# SensorTemperatura.net
KiCad netlist of a schematic drawn in EAGLE
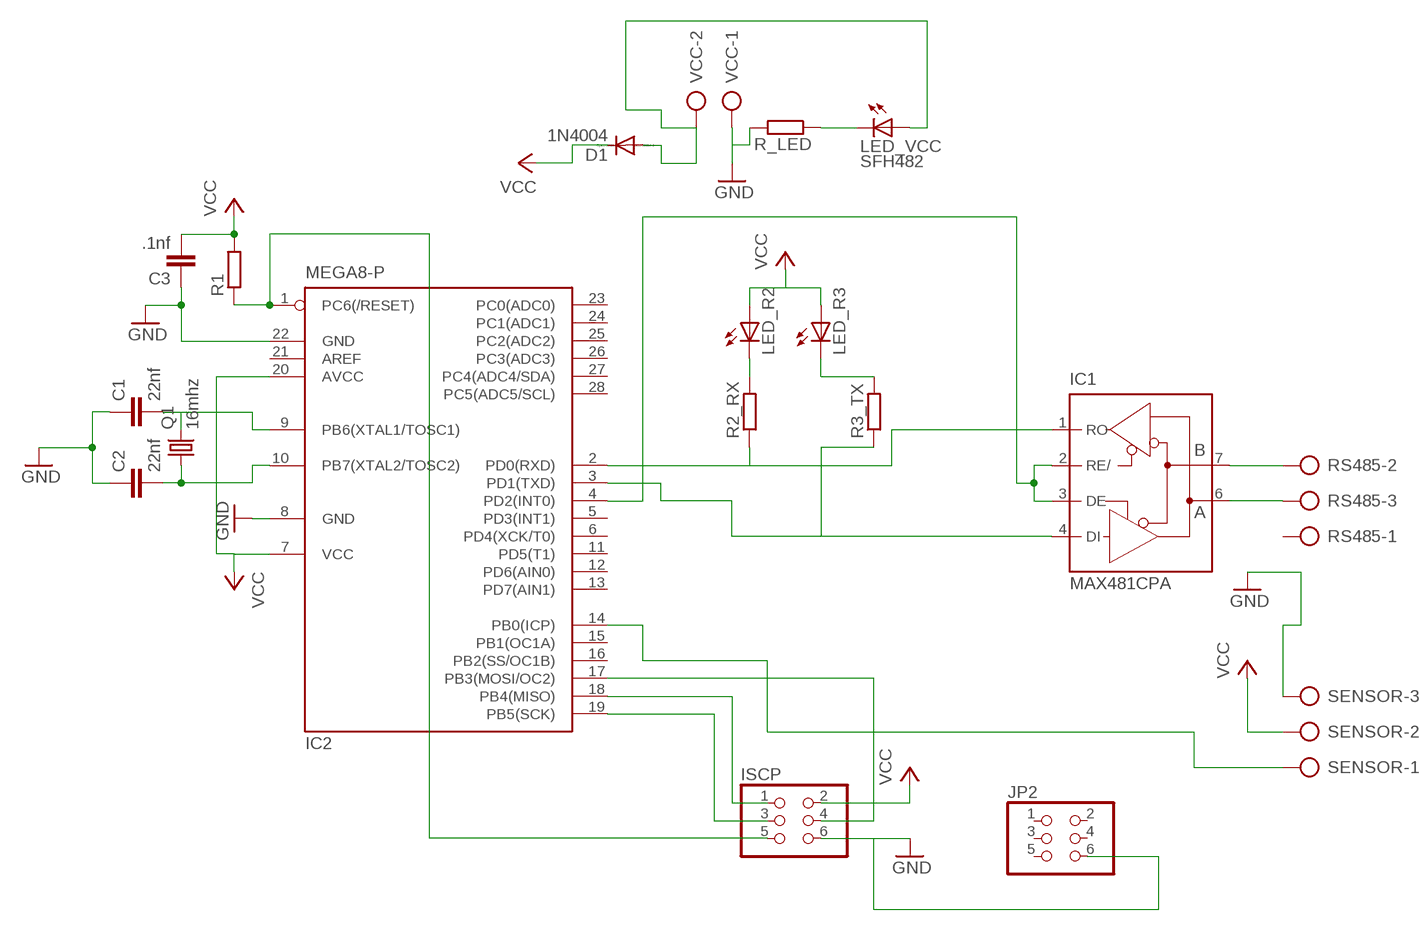
[diagram p0: schematic, sheet 1]

(export (version "E")
  (design (tool "Eeschema 10.0.6"))
  (components
    (comp (ref "C1")
      (value "22nf")
      (footprint "eagle-import:C025-040X050")
      (libsource (lib "eagle-import") (part "C-EU025-040X050"))
    )
    (comp (ref "C2")
      (value "22nf")
      (footprint "eagle-import:C025-040X050")
      (libsource (lib "eagle-import") (part "C-EU025-040X050"))
    )
    (comp (ref "C3")
      (value ".1nf")
      (footprint "eagle-import:C025-040X050")
      (libsource (lib "eagle-import") (part "C-EU025-040X050"))
    )
    (comp (ref "D1")
      (value "1N4004")
      (footprint "eagle-import:DO41-10")
      (libsource (lib "eagle-import") (part "1N4004"))
    )
    (comp (ref "IC1")
      (value "MAX481CPA")
      (footprint "eagle-import:DIL08")
      (fields (field (name "MPN") "MAX481CPA+"))
      (libsource (lib "eagle-import") (part "MAX481CPA"))
    )
    (comp (ref "IC2")
      (value "MEGA8-P")
      (footprint "eagle-import:DIL28-3")
      (libsource (lib "eagle-import") (part "MEGA8-P"))
    )
    (comp (ref "ISCP")
      (value "PINHD-2X3")
      (footprint "eagle-import:2X03")
      (libsource (lib "eagle-import") (part "PINHD-2X3"))
    )
    (comp (ref "JP2")
      (value "PINHD-2X3")
      (footprint "eagle-import:2X03")
      (libsource (lib "eagle-import") (part "PINHD-2X3"))
    )
    (comp (ref "LED_R2")
      (value "SFH482")
      (footprint "eagle-import:SFH482")
      (libsource (lib "eagle-import") (part "SFH482"))
    )
    (comp (ref "LED_R3")
      (value "SFH482")
      (footprint "eagle-import:SFH482")
      (libsource (lib "eagle-import") (part "SFH482"))
    )
    (comp (ref "LED_VCC")
      (value "SFH482")
      (footprint "eagle-import:SFH482")
      (libsource (lib "eagle-import") (part "SFH482"))
    )
    (comp (ref "Q1")
      (value "16mhz")
      (footprint "eagle-import:HC49U-V")
      (libsource (lib "eagle-import") (part "CRYSTALHC49U-V"))
    )
    (comp (ref "R1")
      (value "R-EU_0204/7")
      (footprint "eagle-import:0204_7")
      (libsource (lib "eagle-import") (part "R-EU_0204/7"))
    )
    (comp (ref "R2_RX")
      (value "R-EU_0204/7")
      (footprint "eagle-import:0204_7")
      (libsource (lib "eagle-import") (part "R-EU_0204/7"))
    )
    (comp (ref "R3_TX")
      (value "R-EU_0204/7")
      (footprint "eagle-import:0204_7")
      (libsource (lib "eagle-import") (part "R-EU_0204/7"))
    )
    (comp (ref "RS485")
      (value "AK500/3")
      (footprint "eagle-import:AK500_3")
      (libsource (lib "eagle-import") (part "AK500/3"))
    )
    (comp (ref "R_LED")
      (value "R-EU_0204/7")
      (footprint "eagle-import:0204_7")
      (libsource (lib "eagle-import") (part "R-EU_0204/7"))
    )
    (comp (ref "SENSOR")
      (value "AK500/3")
      (footprint "eagle-import:AK500_3")
      (libsource (lib "eagle-import") (part "AK500/3"))
    )
    (comp (ref "VCC")
      (value "AK500/2")
      (footprint "eagle-import:AK500_2")
      (libsource (lib "eagle-import") (part "AK500/2"))
    )
  )
  (nets
    (net (code "1") (name "GND") (class "Default")
      (node (ref "C1") (pin "1") (pinfunction "1_1") (pintype "passive"))
      (node (ref "C2") (pin "1") (pinfunction "1_1") (pintype "passive"))
      (node (ref "C3") (pin "1") (pinfunction "1_1") (pintype "passive"))
      (node (ref "IC2") (pin "22") (pinfunction "GND_22") (pintype "power_in"))
      (node (ref "IC2") (pin "8") (pinfunction "GND_8") (pintype "power_in"))
      (node (ref "ISCP") (pin "6") (pinfunction "6_6") (pintype "passive"))
      (node (ref "JP2") (pin "6") (pinfunction "6_6") (pintype "passive"))
      (node (ref "R_LED") (pin "2") (pinfunction "2_2") (pintype "passive"))
      (node (ref "SENSOR") (pin "3") (pinfunction "KL_3") (pintype "passive"))
      (node (ref "VCC") (pin "1") (pinfunction "KL_1") (pintype "passive"))
    )
    (net (code "2") (name "Net-(IC1A-A)") (class "Default")
      (node (ref "IC1") (pin "6") (pinfunction "A_6") (pintype "passive"))
      (node (ref "RS485") (pin "3") (pinfunction "KL_3") (pintype "passive"))
    )
    (net (code "3") (name "Net-(IC1A-B)") (class "Default")
      (node (ref "IC1") (pin "7") (pinfunction "B_7") (pintype "passive"))
      (node (ref "RS485") (pin "2") (pinfunction "KL_2") (pintype "passive"))
    )
    (net (code "4") (name "Net-(IC1A-DE)") (class "Default")
      (node (ref "IC1") (pin "2") (pinfunction "RE/_2") (pintype "input"))
      (node (ref "IC1") (pin "3") (pinfunction "DE_3") (pintype "input"))
      (node (ref "IC2") (pin "4") (pinfunction "PD2(INT0)_4") (pintype "bidirectional"))
    )
    (net (code "5") (name "Net-(IC1A-DI)") (class "Default")
      (node (ref "IC1") (pin "4") (pinfunction "DI_4") (pintype "input"))
      (node (ref "IC2") (pin "3") (pinfunction "PD1(TXD)_3") (pintype "bidirectional"))
      (node (ref "R3_TX") (pin "1") (pinfunction "1_1") (pintype "passive"))
    )
    (net (code "6") (name "Net-(IC1A-RO)") (class "Default")
      (node (ref "IC1") (pin "1") (pinfunction "RO_1") (pintype "output"))
      (node (ref "IC2") (pin "2") (pinfunction "PD0(RXD)_2") (pintype "bidirectional"))
      (node (ref "R2_RX") (pin "1") (pinfunction "1_1") (pintype "passive"))
    )
    (net (code "7") (name "Net-(IC2-PB0(ICP))") (class "Default")
      (node (ref "IC2") (pin "14") (pinfunction "PB0(ICP)_14") (pintype "bidirectional"))
      (node (ref "SENSOR") (pin "1") (pinfunction "KL_1") (pintype "passive"))
    )
    (net (code "8") (name "Net-(IC2-PB3(MOSI{slash}OC2))") (class "Default")
      (node (ref "IC2") (pin "17") (pinfunction "PB3(MOSI/OC2)_17") (pintype "bidirectional"))
      (node (ref "ISCP") (pin "4") (pinfunction "4_4") (pintype "passive"))
    )
    (net (code "9") (name "Net-(IC2-PB4(MISO))") (class "Default")
      (node (ref "IC2") (pin "18") (pinfunction "PB4(MISO)_18") (pintype "bidirectional"))
      (node (ref "ISCP") (pin "1") (pinfunction "1_1") (pintype "passive"))
    )
    (net (code "10") (name "Net-(IC2-PB5(SCK))") (class "Default")
      (node (ref "IC2") (pin "19") (pinfunction "PB5(SCK)_19") (pintype "bidirectional"))
      (node (ref "ISCP") (pin "3") (pinfunction "3_3") (pintype "passive"))
    )
    (net (code "11") (name "Net-(IC2-PB6(XTAL1{slash}TOSC1))") (class "Default")
      (node (ref "C1") (pin "2") (pinfunction "2_2") (pintype "passive"))
      (node (ref "IC2") (pin "9") (pinfunction "PB6(XTAL1/TOSC1)_9") (pintype "bidirectional"))
      (node (ref "Q1") (pin "2") (pinfunction "2_2") (pintype "passive"))
    )
    (net (code "12") (name "Net-(IC2-PB7(XTAL2{slash}TOSC2))") (class "Default")
      (node (ref "C2") (pin "2") (pinfunction "2_2") (pintype "passive"))
      (node (ref "IC2") (pin "10") (pinfunction "PB7(XTAL2/TOSC2)_10") (pintype "bidirectional"))
      (node (ref "Q1") (pin "1") (pinfunction "1_1") (pintype "passive"))
    )
    (net (code "13") (name "Net-(IC2-PC6({slash}RESET))") (class "Default")
      (node (ref "IC2") (pin "1") (pinfunction "PC6(/RESET)_1") (pintype "bidirectional"))
      (node (ref "ISCP") (pin "5") (pinfunction "5_5") (pintype "passive"))
      (node (ref "R1") (pin "1") (pinfunction "1_1") (pintype "passive"))
    )
    (net (code "14") (name "Net-(LED_R2-C)") (class "Default")
      (node (ref "LED_R2") (pin "K") (pinfunction "C_K") (pintype "passive"))
      (node (ref "R2_RX") (pin "2") (pinfunction "2_2") (pintype "passive"))
    )
    (net (code "15") (name "Net-(LED_R3-C)") (class "Default")
      (node (ref "LED_R3") (pin "K") (pinfunction "C_K") (pintype "passive"))
      (node (ref "R3_TX") (pin "2") (pinfunction "2_2") (pintype "passive"))
    )
    (net (code "16") (name "Net-(LED_VCC-C)") (class "Default")
      (node (ref "LED_VCC") (pin "K") (pinfunction "C_K") (pintype "passive"))
      (node (ref "R_LED") (pin "1") (pinfunction "1_1") (pintype "passive"))
    )
    (net (code "17") (name "Net-(VCCB-KL)") (class "Default")
      (node (ref "D1") (pin "A") (pinfunction "A_A") (pintype "passive"))
      (node (ref "LED_VCC") (pin "A") (pinfunction "A_A") (pintype "passive"))
      (node (ref "VCC") (pin "2") (pinfunction "KL_2") (pintype "passive"))
    )
    (net (code "18") (name "VCC") (class "Default")
      (node (ref "C3") (pin "2") (pinfunction "2_2") (pintype "passive"))
      (node (ref "D1") (pin "C") (pinfunction "C_C") (pintype "passive"))
      (node (ref "IC2") (pin "20") (pinfunction "AVCC_20") (pintype "power_in"))
      (node (ref "IC2") (pin "7") (pinfunction "VCC_7") (pintype "power_in"))
      (node (ref "ISCP") (pin "2") (pinfunction "2_2") (pintype "passive"))
      (node (ref "LED_R2") (pin "A") (pinfunction "A_A") (pintype "passive"))
      (node (ref "LED_R3") (pin "A") (pinfunction "A_A") (pintype "passive"))
      (node (ref "R1") (pin "2") (pinfunction "2_2") (pintype "passive"))
      (node (ref "SENSOR") (pin "2") (pinfunction "KL_2") (pintype "passive"))
    )
    (net (code "19") (name "unconnected-(IC2-AREF-Pad21)") (class "Default")
      (node (ref "IC2") (pin "21") (pinfunction "AREF_21") (pintype "passive"))
    )
    (net (code "20") (name "unconnected-(IC2-PB1(OC1A)-Pad15)") (class "Default")
      (node (ref "IC2") (pin "15") (pinfunction "PB1(OC1A)_15") (pintype "bidirectional"))
    )
    (net (code "21") (name "unconnected-(IC2-PB2(SS{slash}OC1B)-Pad16)") (class "Default")
      (node (ref "IC2") (pin "16") (pinfunction "PB2(SS/OC1B)_16") (pintype "bidirectional"))
    )
    (net (code "22") (name "unconnected-(IC2-PC0(ADC0)-Pad23)") (class "Default")
      (node (ref "IC2") (pin "23") (pinfunction "PC0(ADC0)_23") (pintype "bidirectional"))
    )
    (net (code "23") (name "unconnected-(IC2-PC1(ADC1)-Pad24)") (class "Default")
      (node (ref "IC2") (pin "24") (pinfunction "PC1(ADC1)_24") (pintype "bidirectional"))
    )
    (net (code "24") (name "unconnected-(IC2-PC2(ADC2)-Pad25)") (class "Default")
      (node (ref "IC2") (pin "25") (pinfunction "PC2(ADC2)_25") (pintype "bidirectional"))
    )
    (net (code "25") (name "unconnected-(IC2-PC3(ADC3)-Pad26)") (class "Default")
      (node (ref "IC2") (pin "26") (pinfunction "PC3(ADC3)_26") (pintype "bidirectional"))
    )
    (net (code "26") (name "unconnected-(IC2-PC4(ADC4{slash}SDA)-Pad27)") (class "Default")
      (node (ref "IC2") (pin "27") (pinfunction "PC4(ADC4/SDA)_27") (pintype "bidirectional"))
    )
    (net (code "27") (name "unconnected-(IC2-PC5(ADC5{slash}SCL)-Pad28)") (class "Default")
      (node (ref "IC2") (pin "28") (pinfunction "PC5(ADC5/SCL)_28") (pintype "bidirectional"))
    )
    (net (code "28") (name "unconnected-(IC2-PD3(INT1)-Pad5)") (class "Default")
      (node (ref "IC2") (pin "5") (pinfunction "PD3(INT1)_5") (pintype "bidirectional"))
    )
    (net (code "29") (name "unconnected-(IC2-PD4(XCK{slash}T0)-Pad6)") (class "Default")
      (node (ref "IC2") (pin "6") (pinfunction "PD4(XCK/T0)_6") (pintype "bidirectional"))
    )
    (net (code "30") (name "unconnected-(IC2-PD5(T1)-Pad11)") (class "Default")
      (node (ref "IC2") (pin "11") (pinfunction "PD5(T1)_11") (pintype "bidirectional"))
    )
    (net (code "31") (name "unconnected-(IC2-PD6(AIN0)-Pad12)") (class "Default")
      (node (ref "IC2") (pin "12") (pinfunction "PD6(AIN0)_12") (pintype "bidirectional"))
    )
    (net (code "32") (name "unconnected-(IC2-PD7(AIN1)-Pad13)") (class "Default")
      (node (ref "IC2") (pin "13") (pinfunction "PD7(AIN1)_13") (pintype "bidirectional"))
    )
    (net (code "33") (name "unconnected-(JP2-Pad1)") (class "Default")
      (node (ref "JP2") (pin "1") (pinfunction "1_1") (pintype "passive"))
    )
    (net (code "34") (name "unconnected-(JP2-Pad2)") (class "Default")
      (node (ref "JP2") (pin "2") (pinfunction "2_2") (pintype "passive"))
    )
    (net (code "35") (name "unconnected-(JP2-Pad3)") (class "Default")
      (node (ref "JP2") (pin "3") (pinfunction "3_3") (pintype "passive"))
    )
    (net (code "36") (name "unconnected-(JP2-Pad4)") (class "Default")
      (node (ref "JP2") (pin "4") (pinfunction "4_4") (pintype "passive"))
    )
    (net (code "37") (name "unconnected-(JP2-Pad5)") (class "Default")
      (node (ref "JP2") (pin "5") (pinfunction "5_5") (pintype "passive"))
    )
    (net (code "38") (name "unconnected-(RS485A-KL-Pad1)") (class "Default")
      (node (ref "RS485") (pin "1") (pinfunction "KL_1") (pintype "passive"))
    )
  )
)
